# v5_a.net
KiCad netlist of a schematic drawn in EasyEDA Pro
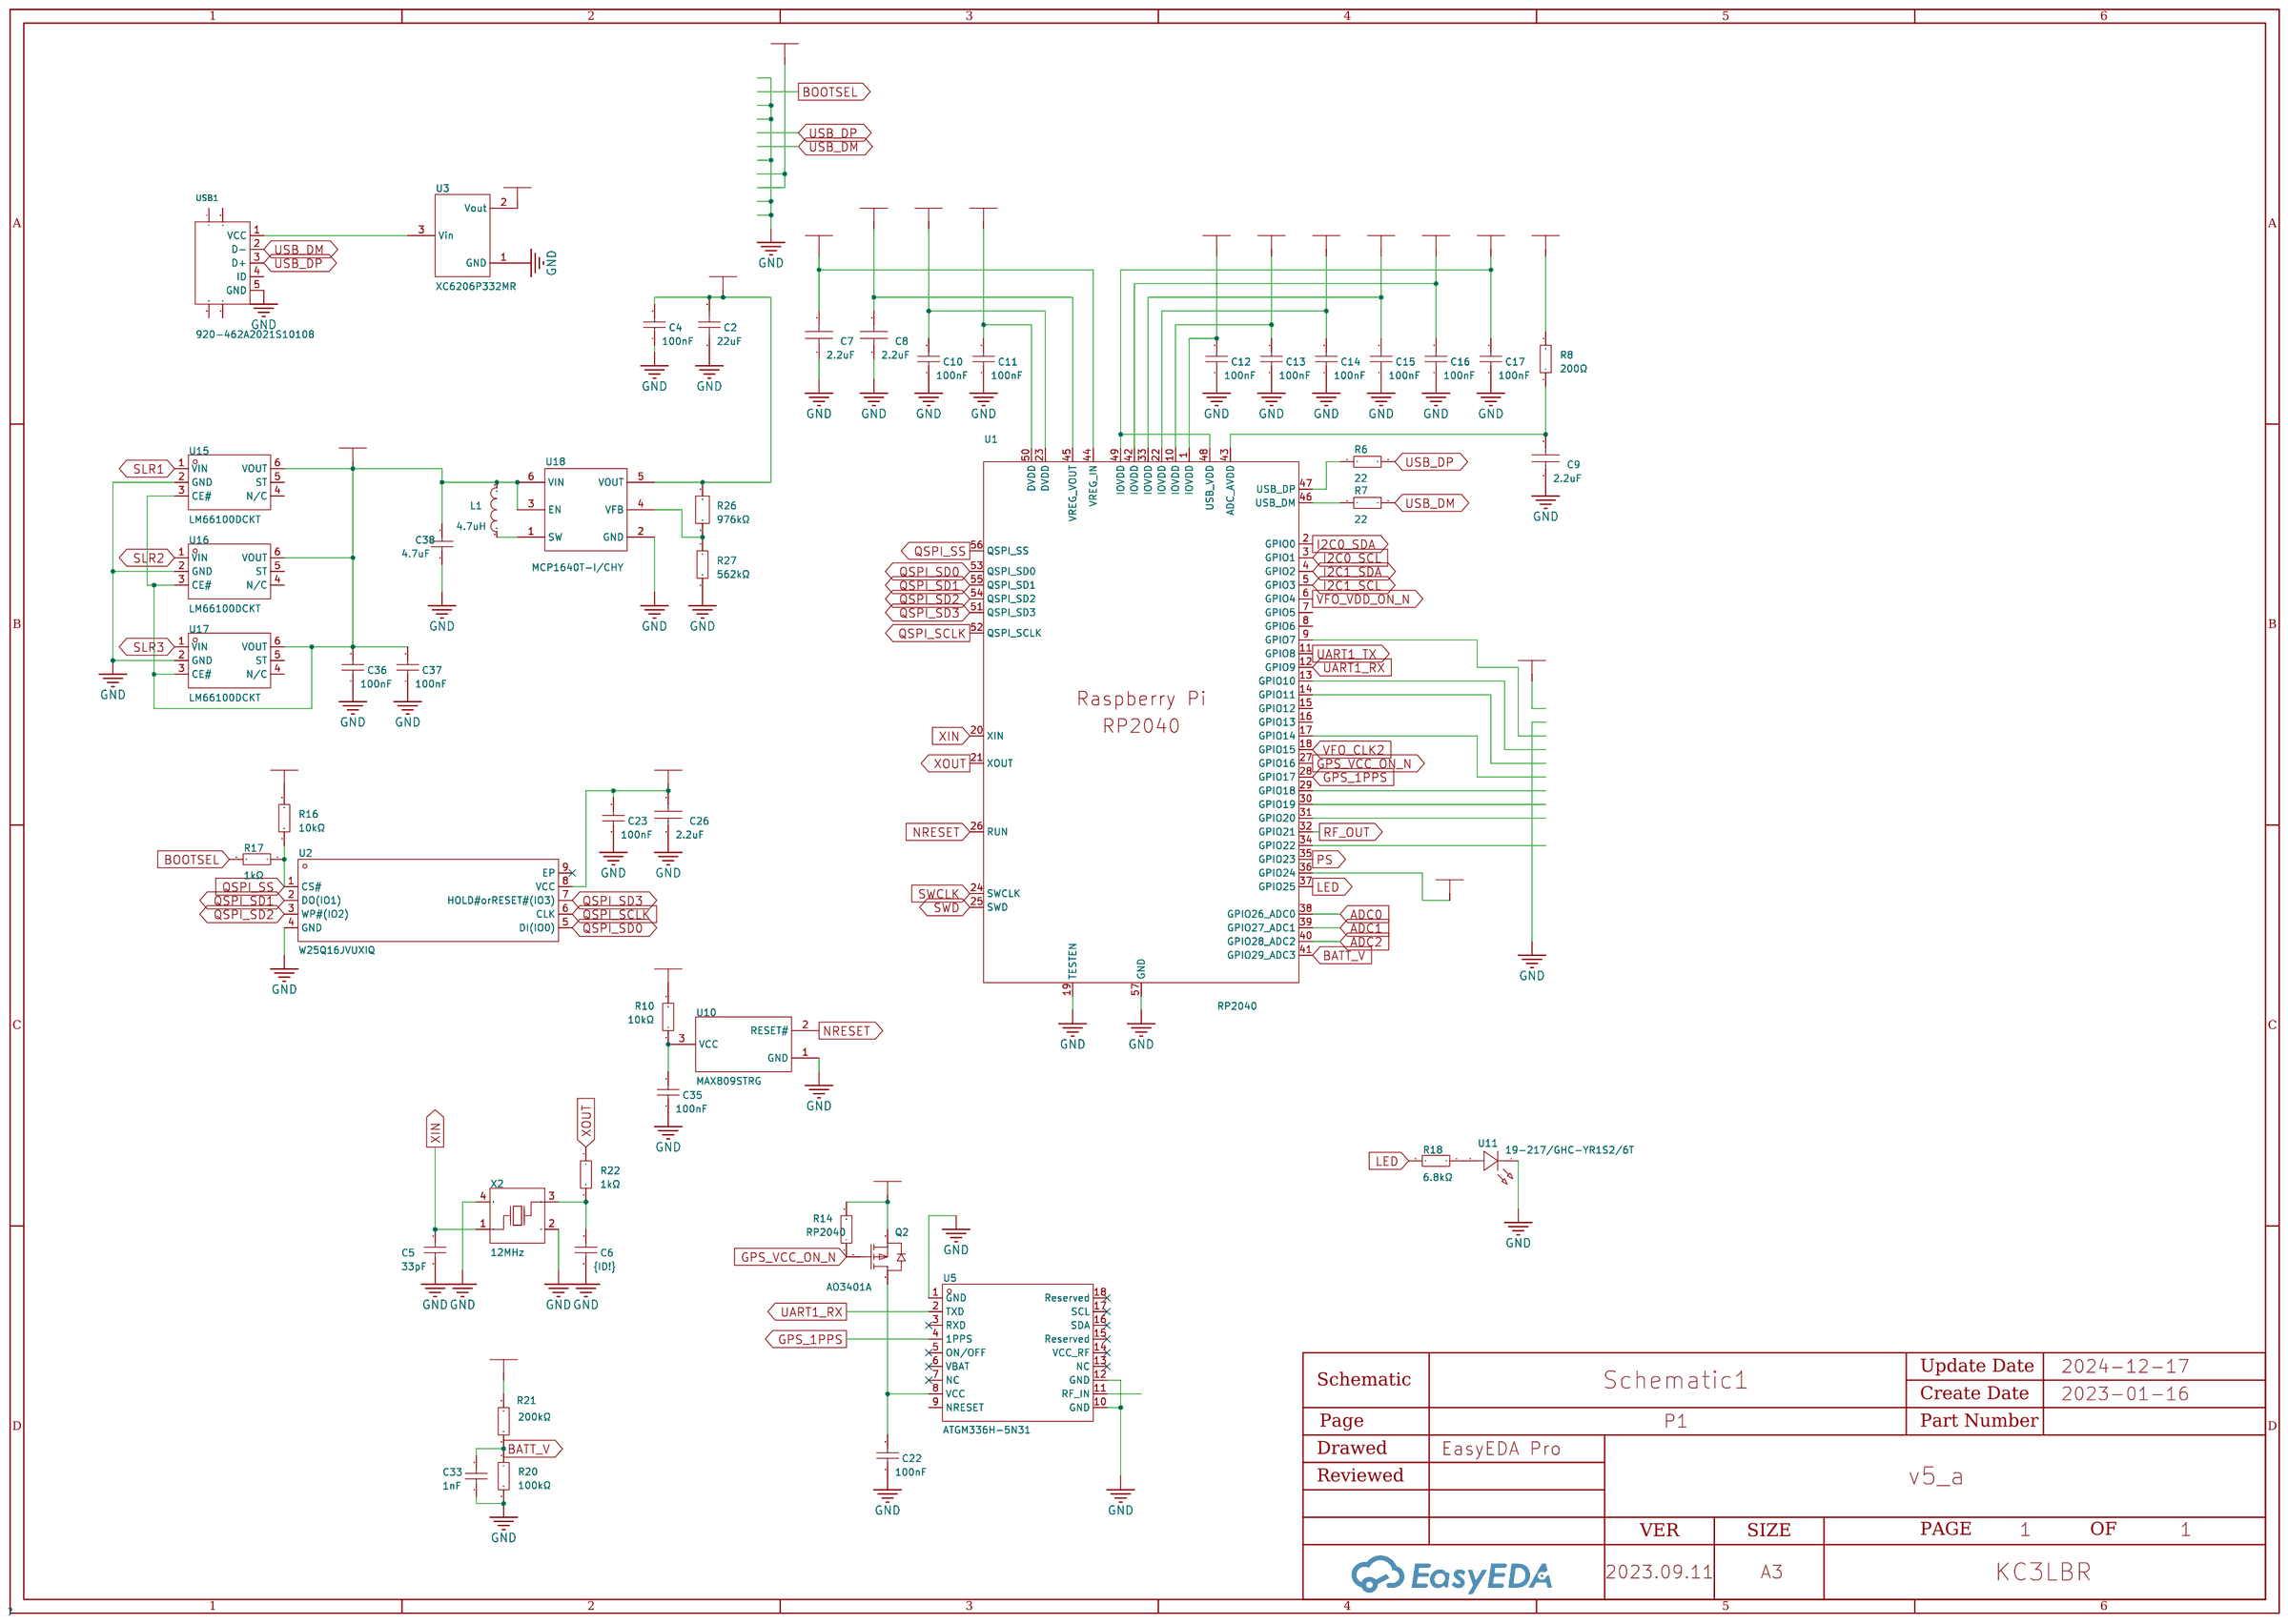
[diagram p0: schematic sheet]

(export (version "E")
  (design (tool "Eeschema 10.0.6"))
  (components
    (comp (ref "C2")
      (value "22uF")
      (footprint "easyedapro:C0603")
      (fields
        (field (name "Manufacturer Part") "CL10A226MQ8NRNC")
        (field (name "Manufacturer") "SAMSUNG(三星)")
      )
      (libsource (lib "easyedapro") (part "CL10A226MQ8NRNC"))
    )
    (comp (ref "C4")
      (value "100nF")
      (footprint "easyedapro:C0402_NEW")
      (fields
        (field (name "Manufacturer Part") "CL05B104KO5NNNC")
        (field (name "Manufacturer") "SAMSUNG(三星)")
      )
      (libsource (lib "easyedapro") (part "CL05B104KO5NNNC"))
    )
    (comp (ref "C5")
      (value "33pF")
      (footprint "easyedapro:C0402")
      (fields (field (name "Manufacturer Part") "0402CG330J500NT") (field (name "Manufacturer") "FH(风华)"))
      (libsource (lib "easyedapro") (part "0402CG330J500NT"))
    )
    (comp (ref "C6")
      (value "33pF")
      (footprint "easyedapro:C0402")
      (fields (field (name "Manufacturer Part") "0402CG330J500NT") (field (name "Manufacturer") "FH(风华)"))
      (libsource (lib "easyedapro") (part "0402CG330J500NT"))
    )
    (comp (ref "C7")
      (value "2.2uF")
      (footprint "easyedapro:C0402")
      (fields
        (field (name "Manufacturer Part") "CL05A225MQ5NSNC")
        (field (name "Manufacturer") "SAMSUNG(三星)")
      )
      (libsource (lib "easyedapro") (part "CL05A225MQ5NSNC"))
    )
    (comp (ref "C8")
      (value "2.2uF")
      (footprint "easyedapro:C0402")
      (fields
        (field (name "Manufacturer Part") "CL05A225MQ5NSNC")
        (field (name "Manufacturer") "SAMSUNG(三星)")
      )
      (libsource (lib "easyedapro") (part "CL05A225MQ5NSNC"))
    )
    (comp (ref "C9")
      (value "2.2uF")
      (footprint "easyedapro:C0402")
      (fields
        (field (name "Manufacturer Part") "CL05A225MQ5NSNC")
        (field (name "Manufacturer") "SAMSUNG(三星)")
      )
      (libsource (lib "easyedapro") (part "CL05A225MQ5NSNC"))
    )
    (comp (ref "C10")
      (value "100nF")
      (footprint "easyedapro:C0402_NEW")
      (fields
        (field (name "Manufacturer Part") "CL05B104KO5NNNC")
        (field (name "Manufacturer") "SAMSUNG(三星)")
      )
      (libsource (lib "easyedapro") (part "CL05B104KO5NNNC"))
    )
    (comp (ref "C11")
      (value "100nF")
      (footprint "easyedapro:C0402_NEW")
      (fields
        (field (name "Manufacturer Part") "CL05B104KO5NNNC")
        (field (name "Manufacturer") "SAMSUNG(三星)")
      )
      (libsource (lib "easyedapro") (part "CL05B104KO5NNNC"))
    )
    (comp (ref "C12")
      (value "100nF")
      (footprint "easyedapro:C0402_NEW")
      (fields
        (field (name "Manufacturer Part") "CL05B104KO5NNNC")
        (field (name "Manufacturer") "SAMSUNG(三星)")
      )
      (libsource (lib "easyedapro") (part "CL05B104KO5NNNC"))
    )
    (comp (ref "C13")
      (value "100nF")
      (footprint "easyedapro:C0402_NEW")
      (fields
        (field (name "Manufacturer Part") "CL05B104KO5NNNC")
        (field (name "Manufacturer") "SAMSUNG(三星)")
      )
      (libsource (lib "easyedapro") (part "CL05B104KO5NNNC"))
    )
    (comp (ref "C14")
      (value "100nF")
      (footprint "easyedapro:C0402_NEW")
      (fields
        (field (name "Manufacturer Part") "CL05B104KO5NNNC")
        (field (name "Manufacturer") "SAMSUNG(三星)")
      )
      (libsource (lib "easyedapro") (part "CL05B104KO5NNNC"))
    )
    (comp (ref "C15")
      (value "100nF")
      (footprint "easyedapro:C0402_NEW")
      (fields
        (field (name "Manufacturer Part") "CL05B104KO5NNNC")
        (field (name "Manufacturer") "SAMSUNG(三星)")
      )
      (libsource (lib "easyedapro") (part "CL05B104KO5NNNC"))
    )
    (comp (ref "C16")
      (value "100nF")
      (footprint "easyedapro:C0402_NEW")
      (fields
        (field (name "Manufacturer Part") "CL05B104KO5NNNC")
        (field (name "Manufacturer") "SAMSUNG(三星)")
      )
      (libsource (lib "easyedapro") (part "CL05B104KO5NNNC"))
    )
    (comp (ref "C17")
      (value "100nF")
      (footprint "easyedapro:C0402_NEW")
      (fields
        (field (name "Manufacturer Part") "CL05B104KO5NNNC")
        (field (name "Manufacturer") "SAMSUNG(三星)")
      )
      (libsource (lib "easyedapro") (part "CL05B104KO5NNNC"))
    )
    (comp (ref "C22")
      (value "100nF")
      (footprint "easyedapro:C0402_NEW")
      (fields
        (field (name "Manufacturer Part") "CL05B104KO5NNNC")
        (field (name "Manufacturer") "SAMSUNG(三星)")
      )
      (libsource (lib "easyedapro") (part "CL05B104KO5NNNC"))
    )
    (comp (ref "C23")
      (value "100nF")
      (footprint "easyedapro:C0402_NEW")
      (fields
        (field (name "Manufacturer Part") "CL05B104KO5NNNC")
        (field (name "Manufacturer") "SAMSUNG(三星)")
      )
      (libsource (lib "easyedapro") (part "CL05B104KO5NNNC"))
    )
    (comp (ref "C26")
      (value "2.2uF")
      (footprint "easyedapro:C0402")
      (fields
        (field (name "Manufacturer Part") "CL05A225MQ5NSNC")
        (field (name "Manufacturer") "SAMSUNG(三星)")
      )
      (libsource (lib "easyedapro") (part "CL05A225MQ5NSNC"))
    )
    (comp (ref "C33")
      (value "1nF")
      (footprint "easyedapro:C0402")
      (fields (field (name "Manufacturer Part") "0402B102K500NT") (field (name "Manufacturer") "FH(风华)"))
      (libsource (lib "easyedapro") (part "0402B102K500NT"))
    )
    (comp (ref "C35")
      (value "100nF")
      (footprint "easyedapro:C0402_NEW")
      (fields
        (field (name "Manufacturer Part") "CL05B104KO5NNNC")
        (field (name "Manufacturer") "SAMSUNG(三星)")
      )
      (libsource (lib "easyedapro") (part "CL05B104KO5NNNC"))
    )
    (comp (ref "C36")
      (value "100nF")
      (footprint "easyedapro:C0402_NEW")
      (fields
        (field (name "Manufacturer Part") "CL05B104KO5NNNC")
        (field (name "Manufacturer") "SAMSUNG(三星)")
      )
      (libsource (lib "easyedapro") (part "CL05B104KO5NNNC"))
    )
    (comp (ref "C37")
      (value "100nF")
      (footprint "easyedapro:C0402_NEW")
      (fields
        (field (name "Manufacturer Part") "CL05B104KO5NNNC")
        (field (name "Manufacturer") "SAMSUNG(三星)")
      )
      (libsource (lib "easyedapro") (part "CL05B104KO5NNNC"))
    )
    (comp (ref "C38")
      (value "4.7uF")
      (footprint "easyedapro:C0603")
      (fields
        (field (name "Manufacturer Part") "CL10A475KO8NNNC")
        (field (name "Manufacturer") "SAMSUNG(三星)")
      )
      (libsource (lib "easyedapro") (part "CL10A475KO8NNNC"))
    )
    (comp (ref "L1")
      (value "4.7uH")
      (footprint "easyedapro:IND-SMD_L2.5-W1.8")
      (fields
        (field (name "Manufacturer Part") "CBC2518T4R7M")
        (field (name "Manufacturer") "TAIYO YUDEN(太诱)")
      )
      (libsource (lib "easyedapro") (part "CBC2518T4R7M"))
    )
    (comp (ref "Q2")
      (value "AO3401A")
      (footprint "easyedapro:SOT-23_L2.9-W1.3-P1.90-LS2.4-BR")
      (fields (field (name "Manufacturer") "AOS"))
      (libsource (lib "easyedapro") (part "AO3401A"))
    )
    (comp (ref "R6")
      (value "22")
      (footprint "easyedapro:R0402")
      (fields
        (field (name "Manufacturer Part") "0402WGF220JTCE")
        (field (name "Manufacturer") "UNI-ROYAL(厚声)")
      )
      (libsource (lib "easyedapro") (part "0402WGF220JTCE"))
    )
    (comp (ref "R7")
      (value "22")
      (footprint "easyedapro:R0402")
      (fields
        (field (name "Manufacturer Part") "0402WGF220JTCE")
        (field (name "Manufacturer") "UNI-ROYAL(厚声)")
      )
      (libsource (lib "easyedapro") (part "0402WGF220JTCE"))
    )
    (comp (ref "R8")
      (value "200Ω")
      (footprint "easyedapro:R0402")
      (fields
        (field (name "Manufacturer Part") "0402WGF2000TCE")
        (field (name "Manufacturer") "UNI-ROYAL(厚声)")
      )
      (libsource (lib "easyedapro") (part "0402WGF2000TCE"))
    )
    (comp (ref "R10")
      (value "10kΩ")
      (footprint "easyedapro:R0402")
      (fields
        (field (name "Manufacturer Part") "0402WGF1002TCE")
        (field (name "Manufacturer") "UNI-ROYAL(厚声)")
      )
      (libsource (lib "easyedapro") (part "0402WGF1002TCE"))
    )
    (comp (ref "R14")
      (value "RP2040")
      (footprint "easyedapro:R0402")
      (fields (field (name "Manufacturer") "Raspberry Pi(树莓派)"))
      (libsource (lib "easyedapro") (part "0402WGF1002TCE"))
    )
    (comp (ref "R16")
      (value "10kΩ")
      (footprint "easyedapro:R0402")
      (fields
        (field (name "Manufacturer Part") "0402WGF1002TCE")
        (field (name "Manufacturer") "UNI-ROYAL(厚声)")
      )
      (libsource (lib "easyedapro") (part "0402WGF1002TCE"))
    )
    (comp (ref "R17")
      (value "1kΩ")
      (footprint "easyedapro:R0402")
      (fields
        (field (name "Manufacturer Part") "0402WGF1001TCE")
        (field (name "Manufacturer") "UNI-ROYAL(厚声)")
      )
      (libsource (lib "easyedapro") (part "0402WGF1001TCE"))
    )
    (comp (ref "R18")
      (value "6.8kΩ")
      (footprint "easyedapro:R0402")
      (fields
        (field (name "Manufacturer Part") "0402WGF6801TCE")
        (field (name "Manufacturer") "UNI-ROYAL(厚声)")
      )
      (libsource (lib "easyedapro") (part "0402WGF6801TCE"))
    )
    (comp (ref "R20")
      (value "100kΩ")
      (footprint "easyedapro:R0402")
      (fields
        (field (name "Manufacturer Part") "0402WGF1003TCE")
        (field (name "Manufacturer") "UNI-ROYAL(厚声)")
      )
      (libsource (lib "easyedapro") (part "0402WGF1003TCE"))
    )
    (comp (ref "R21")
      (value "200kΩ")
      (footprint "easyedapro:R0402")
      (fields
        (field (name "Manufacturer Part") "0402WGF2003TCE")
        (field (name "Manufacturer") "UNI-ROYAL(厚声)")
      )
      (libsource (lib "easyedapro") (part "0402WGF2003TCE"))
    )
    (comp (ref "R22")
      (value "1kΩ")
      (footprint "easyedapro:R0402")
      (fields
        (field (name "Manufacturer Part") "0402WGF1001TCE")
        (field (name "Manufacturer") "UNI-ROYAL(厚声)")
      )
      (libsource (lib "easyedapro") (part "0402WGF1001TCE"))
    )
    (comp (ref "R26")
      (value "976kΩ")
      (footprint "easyedapro:R0402")
      (fields (field (name "Manufacturer Part") "RC0402FR-07976KL") (field (name "Manufacturer") "YAGEO(国巨)"))
      (libsource (lib "easyedapro") (part "RC0402FR-07976KL"))
    )
    (comp (ref "R27")
      (value "562kΩ")
      (footprint "easyedapro:R0402")
      (fields (field (name "Manufacturer Part") "RC0402FR-07562KL") (field (name "Manufacturer") "YAGEO(国巨)"))
      (libsource (lib "easyedapro") (part "RC0402FR-07562KL"))
    )
    (comp (ref "U1")
      (value "RP2040")
      (footprint "easyedapro:LQFN-56_L7.0-W7.0-P0.4-EP")
      (fields (field (name "Manufacturer") "Raspberry Pi(树莓派)"))
      (libsource (lib "easyedapro") (part "RP2040"))
    )
    (comp (ref "U2")
      (value "W25Q16JVUXIQ")
      (footprint "easyedapro:USON-8_L3.0-W2.0-P0.50-BL-EP")
      (fields (field (name "Manufacturer") "WINBOND(华邦)"))
      (libsource (lib "easyedapro") (part "W25Q16JVUXIQ"))
    )
    (comp (ref "U3")
      (value "XC6206P332MR")
      (footprint "easyedapro:SOT-23-3_L2.9-W1.6-P1.90-LS2.8-BR")
      (fields (field (name "Manufacturer") "GOODWORK(固得沃克)"))
      (libsource (lib "easyedapro") (part "XC6206P332MR"))
    )
    (comp (ref "U5")
      (value "ATGM336H-5N31")
      (footprint "easyedapro:GPSM-SMD_ATGM336H-TR")
      (fields (field (name "Manufacturer") "杭州中科微"))
      (libsource (lib "easyedapro") (part "ATGM336H-5N31"))
    )
    (comp (ref "U10")
      (value "MAX809STRG")
      (footprint "easyedapro:SOT-23-3_L2.9-W1.6-P1.90-LS2.8-BR")
      (fields (field (name "Manufacturer") "onsemi(安森美)"))
      (libsource (lib "easyedapro") (part "MAX809STRG"))
    )
    (comp (ref "U11")
      (value "19-217/GHC-YR1S2/6T")
      (footprint "easyedapro:LED0603-RD_GREEN")
      (fields (field (name "Manufacturer") "EVERLIGHT(亿光)"))
      (libsource (lib "easyedapro") (part "19-217/GHC-YR1S2/6T"))
    )
    (comp (ref "U15")
      (value "LM66100DCKT")
      (footprint "easyedapro:SC-70-6_L2.0-W1.3-P0.65-LS2.1-BL")
      (fields (field (name "Manufacturer") "TI(德州仪器)"))
      (libsource (lib "easyedapro") (part "LM66100DCKT"))
    )
    (comp (ref "U16")
      (value "LM66100DCKT")
      (footprint "easyedapro:SC-70-6_L2.0-W1.3-P0.65-LS2.1-BL")
      (fields (field (name "Manufacturer") "TI(德州仪器)"))
      (libsource (lib "easyedapro") (part "LM66100DCKT"))
    )
    (comp (ref "U17")
      (value "LM66100DCKT")
      (footprint "easyedapro:SC-70-6_L2.0-W1.3-P0.65-LS2.1-BL")
      (fields (field (name "Manufacturer") "TI(德州仪器)"))
      (libsource (lib "easyedapro") (part "LM66100DCKT"))
    )
    (comp (ref "U18")
      (value "MCP1640T-I/CHY")
      (footprint "easyedapro:SOT-23-6_L2.9-W1.6-P0.95-LS2.8-BR")
      (fields (field (name "Manufacturer") "MICROCHIP(美国微芯)"))
      (libsource (lib "easyedapro") (part "MCP1640T-I/CHY"))
    )
    (comp (ref "USB1")
      (value "920-462A2021S10108")
      (footprint "easyedapro:MINI-USB-SMD_C105424")
      (description "Connector Type:Mini-B Standard:USB 2.0 Gender:Female Number of Ports:1 Number of Contacts:5P")
      (fields (field (name "Manufacturer") "精拓金"))
      (libsource (lib "easyedapro") (part "USB-MINI-SMD-9.2X9.4-H3.7"))
    )
    (comp (ref "X2")
      (value "12MHz")
      (footprint "easyedapro:OSC-SMD_4P-L3.2-W2.5-BL")
      (fields (field (name "Manufacturer Part") "X322512MSB4SI") (field (name "Manufacturer") "YXC(扬兴晶振)"))
      (libsource (lib "easyedapro") (part "X322512MSB4SI"))
    )
  )
  (nets
    (net (code "1") (name "1V1") (class "Default")
      (node (ref "C10") (pin "2") (pinfunction "2_2") (pintype "input"))
      (node (ref "C11") (pin "2") (pinfunction "2_2") (pintype "input"))
      (node (ref "C8") (pin "2") (pinfunction "2_2") (pintype "input"))
      (node (ref "U1") (pin "23") (pinfunction "DVDD_23") (pintype "bidirectional"))
      (node (ref "U1") (pin "45") (pinfunction "VREG_VOUT_45") (pintype "bidirectional"))
      (node (ref "U1") (pin "50") (pinfunction "DVDD_50") (pintype "bidirectional"))
    )
    (net (code "2") (name "3V3") (class "Default")
      (node (ref "C12") (pin "2") (pinfunction "2_2") (pintype "input"))
      (node (ref "C13") (pin "2") (pinfunction "2_2") (pintype "input"))
      (node (ref "C14") (pin "2") (pinfunction "2_2") (pintype "input"))
      (node (ref "C15") (pin "2") (pinfunction "2_2") (pintype "input"))
      (node (ref "C16") (pin "2") (pinfunction "2_2") (pintype "input"))
      (node (ref "C17") (pin "2") (pinfunction "2_2") (pintype "input"))
      (node (ref "C2") (pin "2") (pinfunction "2_2") (pintype "input"))
      (node (ref "C23") (pin "2") (pinfunction "2_2") (pintype "input"))
      (node (ref "C26") (pin "2") (pinfunction "2_2") (pintype "input"))
      (node (ref "C4") (pin "2") (pinfunction "2_2") (pintype "input"))
      (node (ref "C7") (pin "2") (pinfunction "2_2") (pintype "input"))
      (node (ref "Q2") (pin "2") (pinfunction "S_2") (pintype "input"))
      (node (ref "R10") (pin "2") (pinfunction "2_2") (pintype "input"))
      (node (ref "R14") (pin "2") (pinfunction "2_2") (pintype "input"))
      (node (ref "R16") (pin "2") (pinfunction "2_2") (pintype "input"))
      (node (ref "R26") (pin "2") (pinfunction "2_2") (pintype "unspecified"))
      (node (ref "R8") (pin "2") (pinfunction "2_2") (pintype "input"))
      (node (ref "U1") (pin "1") (pinfunction "IOVDD_1") (pintype "bidirectional"))
      (node (ref "U1") (pin "10") (pinfunction "IOVDD_10") (pintype "bidirectional"))
      (node (ref "U1") (pin "22") (pinfunction "IOVDD_22") (pintype "bidirectional"))
      (node (ref "U1") (pin "33") (pinfunction "IOVDD_33") (pintype "bidirectional"))
      (node (ref "U1") (pin "36") (pinfunction "GPIO24_36") (pintype "bidirectional"))
      (node (ref "U1") (pin "42") (pinfunction "IOVDD_42") (pintype "bidirectional"))
      (node (ref "U1") (pin "44") (pinfunction "VREG_IN_44") (pintype "bidirectional"))
      (node (ref "U1") (pin "48") (pinfunction "USB_VDD_48") (pintype "bidirectional"))
      (node (ref "U1") (pin "49") (pinfunction "IOVDD_49") (pintype "bidirectional"))
      (node (ref "U18") (pin "5") (pinfunction "VOUT_5") (pintype "input"))
      (node (ref "U2") (pin "8") (pinfunction "VCC_8") (pintype "input"))
      (node (ref "U3") (pin "2") (pinfunction "Vout_2") (pintype "input"))
    )
    (net (code "3") (name "ADC0") (class "Default")
      (node (ref "U1") (pin "38") (pinfunction "GPIO26_ADC0_38") (pintype "bidirectional"))
    )
    (net (code "4") (name "ADC1") (class "Default")
      (node (ref "U1") (pin "39") (pinfunction "GPIO27_ADC1_39") (pintype "bidirectional"))
    )
    (net (code "5") (name "ADC2") (class "Default")
      (node (ref "U1") (pin "40") (pinfunction "GPIO28_ADC2_40") (pintype "bidirectional"))
    )
    (net (code "6") (name "BATT_V") (class "Default")
      (node (ref "C33") (pin "2") (pinfunction "2_2") (pintype "input"))
      (node (ref "R20") (pin "1") (pinfunction "1_1") (pintype "input"))
      (node (ref "R21") (pin "1") (pinfunction "1_1") (pintype "input"))
      (node (ref "U1") (pin "41") (pinfunction "GPIO29_ADC3_41") (pintype "bidirectional"))
    )
    (net (code "7") (name "BOOTSEL") (class "Default")
      (node (ref "R17") (pin "2") (pinfunction "2_2") (pintype "input"))
    )
    (net (code "8") (name "GND") (class "Default")
      (node (ref "C10") (pin "1") (pinfunction "1_1") (pintype "input"))
      (node (ref "C11") (pin "1") (pinfunction "1_1") (pintype "input"))
      (node (ref "C12") (pin "1") (pinfunction "1_1") (pintype "input"))
      (node (ref "C13") (pin "1") (pinfunction "1_1") (pintype "input"))
      (node (ref "C14") (pin "1") (pinfunction "1_1") (pintype "input"))
      (node (ref "C15") (pin "1") (pinfunction "1_1") (pintype "input"))
      (node (ref "C16") (pin "1") (pinfunction "1_1") (pintype "input"))
      (node (ref "C17") (pin "1") (pinfunction "1_1") (pintype "input"))
      (node (ref "C2") (pin "1") (pinfunction "1_1") (pintype "input"))
      (node (ref "C22") (pin "1") (pinfunction "1_1") (pintype "input"))
      (node (ref "C23") (pin "1") (pinfunction "1_1") (pintype "input"))
      (node (ref "C26") (pin "1") (pinfunction "1_1") (pintype "input"))
      (node (ref "C33") (pin "1") (pinfunction "1_1") (pintype "input"))
      (node (ref "C35") (pin "1") (pinfunction "1_1") (pintype "input"))
      (node (ref "C36") (pin "1") (pinfunction "1_1") (pintype "input"))
      (node (ref "C37") (pin "1") (pinfunction "1_1") (pintype "input"))
      (node (ref "C38") (pin "1") (pinfunction "1_1") (pintype "input"))
      (node (ref "C4") (pin "1") (pinfunction "1_1") (pintype "input"))
      (node (ref "C5") (pin "1") (pinfunction "1_1") (pintype "input"))
      (node (ref "C6") (pin "1") (pinfunction "1_1") (pintype "input"))
      (node (ref "C7") (pin "1") (pinfunction "1_1") (pintype "input"))
      (node (ref "C8") (pin "1") (pinfunction "1_1") (pintype "input"))
      (node (ref "C9") (pin "1") (pinfunction "1_1") (pintype "input"))
      (node (ref "R20") (pin "2") (pinfunction "2_2") (pintype "input"))
      (node (ref "R27") (pin "1") (pinfunction "1_1") (pintype "unspecified"))
      (node (ref "U1") (pin "19") (pinfunction "TESTEN_19") (pintype "input"))
      (node (ref "U1") (pin "57") (pinfunction "GND_57") (pintype "bidirectional"))
      (node (ref "U10") (pin "1") (pinfunction "GND_1") (pintype "input"))
      (node (ref "U11") (pin "1") (pinfunction "K_1") (pintype "unspecified"))
      (node (ref "U15") (pin "2") (pinfunction "GND_2") (pintype "input"))
      (node (ref "U16") (pin "2") (pinfunction "GND_2") (pintype "input"))
      (node (ref "U17") (pin "2") (pinfunction "GND_2") (pintype "input"))
      (node (ref "U18") (pin "2") (pinfunction "GND_2") (pintype "input"))
      (node (ref "U2") (pin "4") (pinfunction "GND_4") (pintype "input"))
      (node (ref "U3") (pin "1") (pinfunction "GND_1") (pintype "input"))
      (node (ref "U5") (pin "1") (pinfunction "GND_1") (pintype "input"))
      (node (ref "U5") (pin "10") (pinfunction "GND_10") (pintype "input"))
      (node (ref "U5") (pin "12") (pinfunction "GND_12") (pintype "input"))
      (node (ref "USB1") (pin "5") (pinfunction "GND_5") (pintype "input"))
      (node (ref "X2") (pin "2") (pinfunction "GND_2") (pintype "input"))
      (node (ref "X2") (pin "4") (pinfunction "GND_4") (pintype "input"))
    )
    (net (code "9") (name "GPS_1PPS") (class "Default")
      (node (ref "U1") (pin "28") (pinfunction "GPIO17_28") (pintype "bidirectional"))
      (node (ref "U5") (pin "4") (pinfunction "1PPS_4") (pintype "input"))
    )
    (net (code "10") (name "GPS_VCC_ON_N") (class "Default")
      (node (ref "Q2") (pin "1") (pinfunction "G_1") (pintype "input"))
      (node (ref "R14") (pin "1") (pinfunction "1_1") (pintype "input"))
      (node (ref "U1") (pin "27") (pinfunction "GPIO16_27") (pintype "bidirectional"))
    )
    (net (code "11") (name "I2C0_SCL") (class "Default")
      (node (ref "U1") (pin "3") (pinfunction "GPIO1_3") (pintype "bidirectional"))
    )
    (net (code "12") (name "I2C0_SDA") (class "Default")
      (node (ref "U1") (pin "2") (pinfunction "GPIO0_2") (pintype "bidirectional"))
    )
    (net (code "13") (name "I2C1_SCL") (class "Default")
      (node (ref "U1") (pin "5") (pinfunction "GPIO3_5") (pintype "bidirectional"))
    )
    (net (code "14") (name "I2C1_SDA") (class "Default")
      (node (ref "U1") (pin "4") (pinfunction "GPIO2_4") (pintype "bidirectional"))
    )
    (net (code "15") (name "LED") (class "Default")
      (node (ref "R18") (pin "2") (pinfunction "2_2") (pintype "input"))
      (node (ref "U1") (pin "37") (pinfunction "GPIO25_37") (pintype "bidirectional"))
    )
    (net (code "16") (name "NRESET") (class "Default")
      (node (ref "U1") (pin "26") (pinfunction "RUN_26") (pintype "input"))
      (node (ref "U10") (pin "2") (pinfunction "RESET#_2") (pintype "input"))
    )
    (net (code "17") (name "Net-(Q2-D)") (class "Default")
      (node (ref "C22") (pin "2") (pinfunction "2_2") (pintype "input"))
      (node (ref "Q2") (pin "3") (pinfunction "D_3") (pintype "input"))
      (node (ref "U5") (pin "8") (pinfunction "VCC_8") (pintype "input"))
    )
    (net (code "18") (name "Net-(U1-ADC_AVDD)") (class "Default")
      (node (ref "C9") (pin "2") (pinfunction "2_2") (pintype "input"))
      (node (ref "R8") (pin "1") (pinfunction "1_1") (pintype "input"))
      (node (ref "U1") (pin "43") (pinfunction "ADC_AVDD_43") (pintype "bidirectional"))
    )
    (net (code "19") (name "Net-(U1-USB_DM)") (class "Default")
      (node (ref "R7") (pin "1") (pinfunction "1_1") (pintype "input"))
      (node (ref "U1") (pin "46") (pinfunction "USB_DM_46") (pintype "bidirectional"))
    )
    (net (code "20") (name "Net-(U1-USB_DP)") (class "Default")
      (node (ref "R6") (pin "1") (pinfunction "1_1") (pintype "input"))
      (node (ref "U1") (pin "47") (pinfunction "USB_DP_47") (pintype "bidirectional"))
    )
    (net (code "21") (name "Net-(U3-Vin)") (class "Default")
      (node (ref "U3") (pin "3") (pinfunction "Vin_3") (pintype "input"))
      (node (ref "USB1") (pin "1") (pinfunction "VCC_1") (pintype "input"))
    )
    (net (code "22") (name "Net-(U10-VCC)") (class "Default")
      (node (ref "C35") (pin "2") (pinfunction "2_2") (pintype "input"))
      (node (ref "R10") (pin "1") (pinfunction "1_1") (pintype "input"))
      (node (ref "U10") (pin "3") (pinfunction "VCC_3") (pintype "input"))
    )
    (net (code "23") (name "Net-(U11-A)") (class "Default")
      (node (ref "R18") (pin "1") (pinfunction "1_1") (pintype "input"))
      (node (ref "U11") (pin "2") (pinfunction "A_2") (pintype "unspecified"))
    )
    (net (code "24") (name "Net-(U18-SW)") (class "Default")
      (node (ref "L1") (pin "1") (pinfunction "1_1") (pintype "input"))
      (node (ref "U18") (pin "1") (pinfunction "SW_1") (pintype "input"))
    )
    (net (code "25") (name "Net-(U18-VFB)") (class "Default")
      (node (ref "R26") (pin "1") (pinfunction "1_1") (pintype "unspecified"))
      (node (ref "R27") (pin "2") (pinfunction "2_2") (pintype "unspecified"))
      (node (ref "U18") (pin "4") (pinfunction "VFB_4") (pintype "input"))
    )
    (net (code "26") (name "Net-(X2-OSC2)") (class "Default")
      (node (ref "C6") (pin "2") (pinfunction "2_2") (pintype "input"))
      (node (ref "R22") (pin "2") (pinfunction "2_2") (pintype "input"))
      (node (ref "X2") (pin "3") (pinfunction "OSC2_3") (pintype "input"))
    )
    (net (code "27") (name "PS") (class "Default")
      (node (ref "U1") (pin "35") (pinfunction "GPIO23_35") (pintype "bidirectional"))
    )
    (net (code "28") (name "QSPI_SCLK") (class "Default")
      (node (ref "U1") (pin "52") (pinfunction "QSPI_SCLK_52") (pintype "output"))
      (node (ref "U2") (pin "6") (pinfunction "CLK_6") (pintype "input"))
    )
    (net (code "29") (name "QSPI_SD0") (class "Default")
      (node (ref "U1") (pin "53") (pinfunction "QSPI_SD0_53") (pintype "bidirectional"))
      (node (ref "U2") (pin "5") (pinfunction "DI(IO0)_5") (pintype "input"))
    )
    (net (code "30") (name "QSPI_SD1") (class "Default")
      (node (ref "U1") (pin "55") (pinfunction "QSPI_SD1_55") (pintype "bidirectional"))
      (node (ref "U2") (pin "2") (pinfunction "DO(IO1)_2") (pintype "input"))
    )
    (net (code "31") (name "QSPI_SD2") (class "Default")
      (node (ref "U1") (pin "54") (pinfunction "QSPI_SD2_54") (pintype "bidirectional"))
      (node (ref "U2") (pin "3") (pinfunction "WP#(IO2)_3") (pintype "input"))
    )
    (net (code "32") (name "QSPI_SD3") (class "Default")
      (node (ref "U1") (pin "51") (pinfunction "QSPI_SD3_51") (pintype "bidirectional"))
      (node (ref "U2") (pin "7") (pinfunction "HOLD#orRESET#(IO3)_7") (pintype "input"))
    )
    (net (code "33") (name "QSPI_SS") (class "Default")
      (node (ref "R16") (pin "1") (pinfunction "1_1") (pintype "input"))
      (node (ref "R17") (pin "1") (pinfunction "1_1") (pintype "input"))
      (node (ref "U1") (pin "56") (pinfunction "QSPI_SS_56") (pintype "bidirectional"))
      (node (ref "U2") (pin "1") (pinfunction "CS#_1") (pintype "input"))
    )
    (net (code "34") (name "RF_OUT") (class "Default")
      (node (ref "U1") (pin "32") (pinfunction "GPIO21_32") (pintype "bidirectional"))
    )
    (net (code "35") (name "SLR1") (class "Default")
      (node (ref "U15") (pin "1") (pinfunction "VIN_1") (pintype "input"))
    )
    (net (code "36") (name "SLR2") (class "Default")
      (node (ref "U16") (pin "1") (pinfunction "VIN_1") (pintype "input"))
    )
    (net (code "37") (name "SLR3") (class "Default")
      (node (ref "U17") (pin "1") (pinfunction "VIN_1") (pintype "input"))
    )
    (net (code "38") (name "SWCLK") (class "Default")
      (node (ref "U1") (pin "24") (pinfunction "SWCLK_24") (pintype "output"))
    )
    (net (code "39") (name "SWD") (class "Default")
      (node (ref "U1") (pin "25") (pinfunction "SWD_25") (pintype "bidirectional"))
    )
    (net (code "40") (name "UART1_RX") (class "Default")
      (node (ref "U1") (pin "12") (pinfunction "GPIO9_12") (pintype "bidirectional"))
      (node (ref "U5") (pin "2") (pinfunction "TXD_2") (pintype "input"))
    )
    (net (code "41") (name "UART1_TX") (class "Default")
      (node (ref "U1") (pin "11") (pinfunction "GPIO8_11") (pintype "bidirectional"))
    )
    (net (code "42") (name "USB_DM") (class "Default")
      (node (ref "R7") (pin "2") (pinfunction "2_2") (pintype "input"))
      (node (ref "USB1") (pin "2") (pinfunction "D-_2") (pintype "input"))
    )
    (net (code "43") (name "USB_DP") (class "Default")
      (node (ref "R6") (pin "2") (pinfunction "2_2") (pintype "input"))
      (node (ref "USB1") (pin "3") (pinfunction "D+_3") (pintype "input"))
    )
    (net (code "44") (name "VBUS") (class "Default")
      (node (ref "C36") (pin "2") (pinfunction "2_2") (pintype "input"))
      (node (ref "C37") (pin "2") (pinfunction "2_2") (pintype "input"))
      (node (ref "C38") (pin "2") (pinfunction "2_2") (pintype "input"))
      (node (ref "L1") (pin "2") (pinfunction "2_2") (pintype "input"))
      (node (ref "R21") (pin "2") (pinfunction "2_2") (pintype "input"))
      (node (ref "U15") (pin "3") (pinfunction "CE#_3") (pintype "input"))
      (node (ref "U15") (pin "6") (pinfunction "VOUT_6") (pintype "input"))
      (node (ref "U16") (pin "3") (pinfunction "CE#_3") (pintype "input"))
      (node (ref "U16") (pin "6") (pinfunction "VOUT_6") (pintype "input"))
      (node (ref "U17") (pin "3") (pinfunction "CE#_3") (pintype "input"))
      (node (ref "U17") (pin "6") (pinfunction "VOUT_6") (pintype "input"))
      (node (ref "U18") (pin "3") (pinfunction "EN_3") (pintype "input"))
      (node (ref "U18") (pin "6") (pinfunction "VIN_6") (pintype "input"))
    )
    (net (code "45") (name "VFO_CLK2") (class "Default")
      (node (ref "U1") (pin "18") (pinfunction "GPIO15_18") (pintype "bidirectional"))
    )
    (net (code "46") (name "VFO_VDD_ON_N") (class "Default")
      (node (ref "U1") (pin "6") (pinfunction "GPIO4_6") (pintype "bidirectional"))
    )
    (net (code "47") (name "XIN") (class "Default")
      (node (ref "C5") (pin "2") (pinfunction "2_2") (pintype "input"))
      (node (ref "U1") (pin "20") (pinfunction "XIN_20") (pintype "input"))
      (node (ref "X2") (pin "1") (pinfunction "OSC1_1") (pintype "input"))
    )
    (net (code "48") (name "XOUT") (class "Default")
      (node (ref "R22") (pin "1") (pinfunction "1_1") (pintype "input"))
      (node (ref "U1") (pin "21") (pinfunction "XOUT_21") (pintype "input"))
    )
    (net (code "49") (name "unconnected-(U1-GPIO5-Pad7)") (class "Default")
      (node (ref "U1") (pin "7") (pinfunction "GPIO5_7") (pintype "bidirectional"))
    )
    (net (code "50") (name "unconnected-(U1-GPIO6-Pad8)") (class "Default")
      (node (ref "U1") (pin "8") (pinfunction "GPIO6_8") (pintype "bidirectional"))
    )
    (net (code "51") (name "unconnected-(U1-GPIO7-Pad9)") (class "Default")
      (node (ref "U1") (pin "9") (pinfunction "GPIO7_9") (pintype "bidirectional"))
    )
    (net (code "52") (name "unconnected-(U1-GPIO10-Pad13)") (class "Default")
      (node (ref "U1") (pin "13") (pinfunction "GPIO10_13") (pintype "bidirectional"))
    )
    (net (code "53") (name "unconnected-(U1-GPIO11-Pad14)") (class "Default")
      (node (ref "U1") (pin "14") (pinfunction "GPIO11_14") (pintype "bidirectional"))
    )
    (net (code "54") (name "unconnected-(U1-GPIO12-Pad15)") (class "Default")
      (node (ref "U1") (pin "15") (pinfunction "GPIO12_15") (pintype "bidirectional"))
    )
    (net (code "55") (name "unconnected-(U1-GPIO13-Pad16)") (class "Default")
      (node (ref "U1") (pin "16") (pinfunction "GPIO13_16") (pintype "bidirectional"))
    )
    (net (code "56") (name "unconnected-(U1-GPIO14-Pad17)") (class "Default")
      (node (ref "U1") (pin "17") (pinfunction "GPIO14_17") (pintype "bidirectional"))
    )
    (net (code "57") (name "unconnected-(U1-GPIO18-Pad29)") (class "Default")
      (node (ref "U1") (pin "29") (pinfunction "GPIO18_29") (pintype "bidirectional"))
    )
    (net (code "58") (name "unconnected-(U1-GPIO19-Pad30)") (class "Default")
      (node (ref "U1") (pin "30") (pinfunction "GPIO19_30") (pintype "bidirectional"))
    )
    (net (code "59") (name "unconnected-(U1-GPIO20-Pad31)") (class "Default")
      (node (ref "U1") (pin "31") (pinfunction "GPIO20_31") (pintype "bidirectional"))
    )
    (net (code "60") (name "unconnected-(U1-GPIO22-Pad34)") (class "Default")
      (node (ref "U1") (pin "34") (pinfunction "GPIO22_34") (pintype "bidirectional"))
    )
    (net (code "61") (name "unconnected-(U2-EP-Pad9)") (class "Default")
      (node (ref "U2") (pin "9") (pinfunction "EP_9") (pintype "input+no_connect"))
    )
    (net (code "62") (name "unconnected-(U5-NC-Pad7)") (class "Default")
      (node (ref "U5") (pin "7") (pinfunction "NC_7") (pintype "input+no_connect"))
    )
    (net (code "63") (name "unconnected-(U5-NC-Pad13)") (class "Default")
      (node (ref "U5") (pin "13") (pinfunction "NC_13") (pintype "input+no_connect"))
    )
    (net (code "64") (name "unconnected-(U5-NRESET-Pad9)") (class "Default")
      (node (ref "U5") (pin "9") (pinfunction "NRESET_9") (pintype "input"))
    )
    (net (code "65") (name "unconnected-(U5-ON{slash}OFF-Pad5)") (class "Default")
      (node (ref "U5") (pin "5") (pinfunction "ON/OFF_5") (pintype "input+no_connect"))
    )
    (net (code "66") (name "unconnected-(U5-RF_IN-Pad11)") (class "Default")
      (node (ref "U5") (pin "11") (pinfunction "RF_IN_11") (pintype "input"))
    )
    (net (code "67") (name "unconnected-(U5-RXD-Pad3)") (class "Default")
      (node (ref "U5") (pin "3") (pinfunction "RXD_3") (pintype "input+no_connect"))
    )
    (net (code "68") (name "unconnected-(U5-Reserved-Pad15)") (class "Default")
      (node (ref "U5") (pin "15") (pinfunction "Reserved_15") (pintype "input+no_connect"))
    )
    (net (code "69") (name "unconnected-(U5-Reserved-Pad18)") (class "Default")
      (node (ref "U5") (pin "18") (pinfunction "Reserved_18") (pintype "input+no_connect"))
    )
    (net (code "70") (name "unconnected-(U5-SCL-Pad17)") (class "Default")
      (node (ref "U5") (pin "17") (pinfunction "SCL_17") (pintype "input+no_connect"))
    )
    (net (code "71") (name "unconnected-(U5-SDA-Pad16)") (class "Default")
      (node (ref "U5") (pin "16") (pinfunction "SDA_16") (pintype "input+no_connect"))
    )
    (net (code "72") (name "unconnected-(U5-VBAT-Pad6)") (class "Default")
      (node (ref "U5") (pin "6") (pinfunction "VBAT_6") (pintype "input+no_connect"))
    )
    (net (code "73") (name "unconnected-(U5-VCC_RF-Pad14)") (class "Default")
      (node (ref "U5") (pin "14") (pinfunction "VCC_RF_14") (pintype "input+no_connect"))
    )
    (net (code "74") (name "unconnected-(U15-N{slash}C-Pad4)") (class "Default")
      (node (ref "U15") (pin "4") (pinfunction "N/C_4") (pintype "input"))
    )
    (net (code "75") (name "unconnected-(U15-ST-Pad5)") (class "Default")
      (node (ref "U15") (pin "5") (pinfunction "ST_5") (pintype "input"))
    )
    (net (code "76") (name "unconnected-(U16-N{slash}C-Pad4)") (class "Default")
      (node (ref "U16") (pin "4") (pinfunction "N/C_4") (pintype "input"))
    )
    (net (code "77") (name "unconnected-(U16-ST-Pad5)") (class "Default")
      (node (ref "U16") (pin "5") (pinfunction "ST_5") (pintype "input"))
    )
    (net (code "78") (name "unconnected-(U17-N{slash}C-Pad4)") (class "Default")
      (node (ref "U17") (pin "4") (pinfunction "N/C_4") (pintype "input"))
    )
    (net (code "79") (name "unconnected-(U17-ST-Pad5)") (class "Default")
      (node (ref "U17") (pin "5") (pinfunction "ST_5") (pintype "input"))
    )
    (net (code "80") (name "unconnected-(USB1-ID-Pad4)") (class "Default")
      (node (ref "USB1") (pin "4") (pinfunction "ID_4") (pintype "input"))
    )
    (net (code "81") (name "unconnected-(USB1-Pad6)") (class "Default")
      (node (ref "USB1") (pin "6") (pinfunction "6_6") (pintype "input"))
    )
    (net (code "82") (name "unconnected-(USB1-Pad7)") (class "Default")
      (node (ref "USB1") (pin "7") (pinfunction "7_7") (pintype "input"))
    )
    (net (code "83") (name "unconnected-(USB1-Pad8)") (class "Default")
      (node (ref "USB1") (pin "8") (pinfunction "8_8") (pintype "input"))
    )
    (net (code "84") (name "unconnected-(USB1-Pad9)") (class "Default")
      (node (ref "USB1") (pin "9") (pinfunction "9_9") (pintype "input"))
    )
  )
)
